# charging.net
KiCad netlist of a schematic drawn in Altium Designer
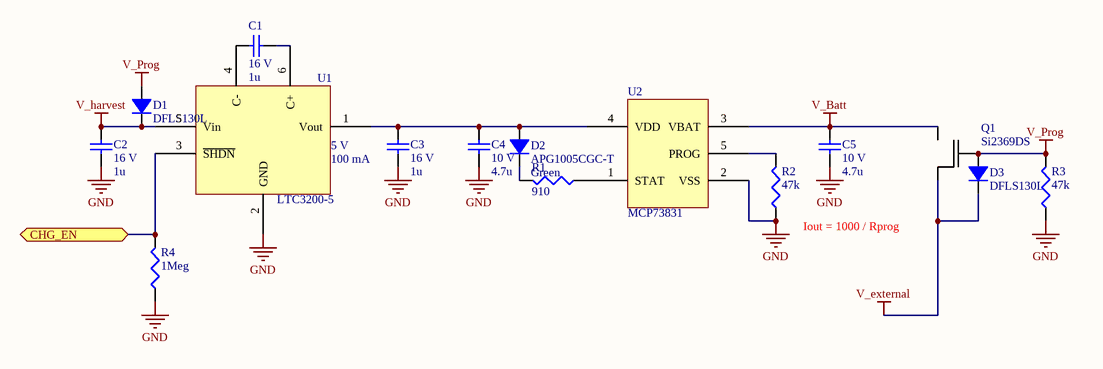
[diagram p0: charging.SchDoc]

(export (version "E")
  (design (tool "Eeschema 10.0.6"))
  (components
    (comp (ref "C1")
      (value "1u")
      (footprint "0603")
      (description "1µF ±10% 16V Ceramic Capacitor X7R 0603")
      (fields
        (field (name "TOLERANCE") "10%")
        (field (name "MANUFACTURER PART NUMBER") "C1608X7R1C105K080AC")
        (field (name "VOLTAGE RATED") "16 V")
      )
      (libsource (lib "capacitors") (part "C1608X7R1C105K080AC"))
    )
    (comp (ref "C2")
      (value "1u")
      (footprint "0603")
      (description "1µF ±10% 16V Ceramic Capacitor X7R 0603")
      (fields
        (field (name "TOLERANCE") "10%")
        (field (name "MANUFACTURER PART NUMBER") "C1608X7R1C105K080AC")
        (field (name "VOLTAGE RATED") "16 V")
      )
      (libsource (lib "capacitors") (part "C1608X7R1C105K080AC"))
    )
    (comp (ref "C3")
      (value "1u")
      (footprint "0603")
      (description "1µF ±10% 16V Ceramic Capacitor X7R 0603")
      (fields
        (field (name "TOLERANCE") "10%")
        (field (name "MANUFACTURER PART NUMBER") "C1608X7R1C105K080AC")
        (field (name "VOLTAGE RATED") "16 V")
      )
      (libsource (lib "capacitors") (part "C1608X7R1C105K080AC"))
    )
    (comp (ref "C4")
      (value "4.7u")
      (footprint "0603")
      (description "4.7µF ±10% 10V Ceramic Capacitor X5R 0603")
      (fields
        (field (name "TOLERANCE") "10%")
        (field (name "VOLTAGE RATED") "10 V")
        (field (name "MANUFACTURER PART NUMBER") "CGB3B1X5R1A475K055AC")
      )
      (libsource (lib "capacitors") (part "CGB3B1X5R1A475K055AC"))
    )
    (comp (ref "C5")
      (value "4.7u")
      (footprint "0603")
      (description "4.7µF ±10% 10V Ceramic Capacitor X5R 0603")
      (fields
        (field (name "TOLERANCE") "10%")
        (field (name "VOLTAGE RATED") "10 V")
        (field (name "MANUFACTURER PART NUMBER") "CGB3B1X5R1A475K055AC")
      )
      (libsource (lib "capacitors") (part "CGB3B1X5R1A475K055AC"))
    )
    (comp (ref "D1")
      (value "DFLS130L")
      (footprint "PowerDI123")
      (description "1.0A SURFACE MOUNT SCHOTTKY BARRIER RECTIFIER")
      (fields (field (name "MANUFACTURER") "Diodes Incorporated") (field (name "POWER") "556 mW"))
      (libsource (lib "diodes") (part "DFLS130L"))
    )
    (comp (ref "D2")
      (value "APG1005CGC-T")
      (footprint "0402 - LED")
      (description "Green 571nm LED Indication - Discrete 2V 0402 (1005 Metric)")
      (fields (field (name "MANUFACTURER") "Kingbright") (field (name "ALTIUM_VALUE") "Green"))
      (libsource (lib "LED") (part "APG1005CGC-T"))
    )
    (comp (ref "D3")
      (value "DFLS130L")
      (footprint "PowerDI123")
      (description "1.0A SURFACE MOUNT SCHOTTKY BARRIER RECTIFIER")
      (fields (field (name "MANUFACTURER") "Diodes Incorporated") (field (name "POWER") "556 mW"))
      (libsource (lib "diodes") (part "DFLS130L"))
    )
    (comp (ref "Q1")
      (value "Si2369DS")
      (footprint "SOT23-3")
      (description "P-Channel 30-V (D-S) MOSFET")
      (libsource (lib "transistors") (part "Si2369DS"))
    )
    (comp (ref "R1")
      (value "910")
      (footprint "0402")
      (description "RES SMD 910 OHM 1% 1/16W 0402")
      (fields (field (name "TOLERANCE") "1%") (field (name "POWER") "1/16 W"))
      (libsource (lib "resistors") (part "CRCW0402910RFKED"))
    )
    (comp (ref "R2")
      (value "47k")
      (footprint "0402")
      (description "RES SMD 47K OHM 1% 1/16W 0402")
      (fields (field (name "TOLERANCE") "1%") (field (name "POWER") "1/16 W"))
      (libsource (lib "resistors") (part "CRCW040247K0FKED"))
    )
    (comp (ref "R3")
      (value "47k")
      (footprint "0402")
      (description "RES SMD 47K OHM 1% 1/16W 0402")
      (fields (field (name "TOLERANCE") "1%") (field (name "POWER") "1/16 W"))
      (libsource (lib "resistors") (part "CRCW040247K0FKED"))
    )
    (comp (ref "R4")
      (value "1Meg")
      (footprint "0402")
      (description "RES SMD 1M OHM 1% 1/16W 0402")
      (fields (field (name "TOLERANCE") "1%") (field (name "POWER") "1/16 W"))
      (libsource (lib "resistors") (part "CRCW04021M00FKED"))
    )
    (comp (ref "U1")
      (value "LTC3200-5")
      (footprint "SOT23-6")
      (description "Low Noise, Regulated   Charge Pump DC/DC Converters")
      (fields (field (name "VOUT") "5 V") (field (name "IOUT") "100 mA"))
      (libsource (lib "voltage regulator") (part "LTC3200ES6-5#TRMPBF"))
    )
    (comp (ref "U2")
      (value "MCP73831")
      (footprint "TSOT23-5")
      (description "Miniature Single-Cell, Fully Integrated Li-Ion,  Li-Polymer Charge Management Controllers")
      (libsource (lib "battery charger") (part "MCP73831"))
    )
  )
  (nets
    (net (code "1") (name "/CHG_EN") (class "Default")
      (node (ref "R4") (pin "1") (pintype "passive"))
      (node (ref "U1") (pin "3") (pinfunction "~{SHDN}_3") (pintype "passive"))
    )
    (net (code "2") (name "GND") (class "Default")
      (node (ref "C2") (pin "1") (pintype "passive"))
      (node (ref "C3") (pin "1") (pintype "passive"))
      (node (ref "C4") (pin "2") (pintype "passive"))
      (node (ref "C5") (pin "2") (pintype "passive"))
      (node (ref "R2") (pin "2") (pintype "passive"))
      (node (ref "R3") (pin "2") (pintype "passive"))
      (node (ref "R4") (pin "2") (pintype "passive"))
      (node (ref "U1") (pin "2") (pinfunction "GND_2") (pintype "passive"))
      (node (ref "U2") (pin "2") (pinfunction "VSS_2") (pintype "passive"))
    )
    (net (code "3") (name "Net-(D2-Pad2)") (class "Default")
      (node (ref "D2") (pin "2") (pintype "passive"))
      (node (ref "R1") (pin "1") (pintype "passive"))
    )
    (net (code "4") (name "Net-(U1-C+)") (class "Default")
      (node (ref "C1") (pin "2") (pintype "passive"))
      (node (ref "U1") (pin "6") (pinfunction "C+_6") (pintype "passive"))
    )
    (net (code "5") (name "Net-(U1-C-)") (class "Default")
      (node (ref "C1") (pin "1") (pintype "passive"))
      (node (ref "U1") (pin "4") (pinfunction "C-_4") (pintype "passive"))
    )
    (net (code "6") (name "Net-(U1-Vout)") (class "Default")
      (node (ref "C3") (pin "2") (pintype "passive"))
      (node (ref "C4") (pin "1") (pintype "passive"))
      (node (ref "D2") (pin "1") (pintype "passive"))
      (node (ref "U1") (pin "1") (pinfunction "Vout_1") (pintype "passive"))
      (node (ref "U2") (pin "4") (pinfunction "VDD_4") (pintype "passive"))
    )
    (net (code "7") (name "Net-(U2-PROG)") (class "Default")
      (node (ref "R2") (pin "1") (pintype "passive"))
      (node (ref "U2") (pin "5") (pinfunction "PROG_5") (pintype "passive"))
    )
    (net (code "8") (name "Net-(U2-STAT)") (class "Default")
      (node (ref "R1") (pin "2") (pintype "passive"))
      (node (ref "U2") (pin "1") (pinfunction "STAT_1") (pintype "passive"))
    )
    (net (code "9") (name "V_Batt") (class "Default")
      (node (ref "C5") (pin "1") (pintype "passive"))
      (node (ref "Q1") (pin "2") (pinfunction "S_2") (pintype "passive"))
      (node (ref "U2") (pin "3") (pinfunction "VBAT_3") (pintype "passive"))
    )
    (net (code "10") (name "V_Prog") (class "Default")
      (node (ref "D1") (pin "1") (pintype "passive"))
      (node (ref "D3") (pin "1") (pintype "passive"))
      (node (ref "Q1") (pin "1") (pinfunction "G_1") (pintype "passive"))
      (node (ref "R3") (pin "1") (pintype "passive"))
    )
    (net (code "11") (name "V_external") (class "Default")
      (node (ref "D3") (pin "2") (pintype "passive"))
      (node (ref "Q1") (pin "3") (pinfunction "D_3") (pintype "passive"))
    )
    (net (code "12") (name "V_harvest") (class "Default")
      (node (ref "C2") (pin "2") (pintype "passive"))
      (node (ref "D1") (pin "2") (pintype "passive"))
      (node (ref "U1") (pin "5") (pinfunction "Vin_5") (pintype "passive"))
    )
  )
)
